# MB1297_MEMS.net
KiCad netlist of a schematic drawn in Altium Designer
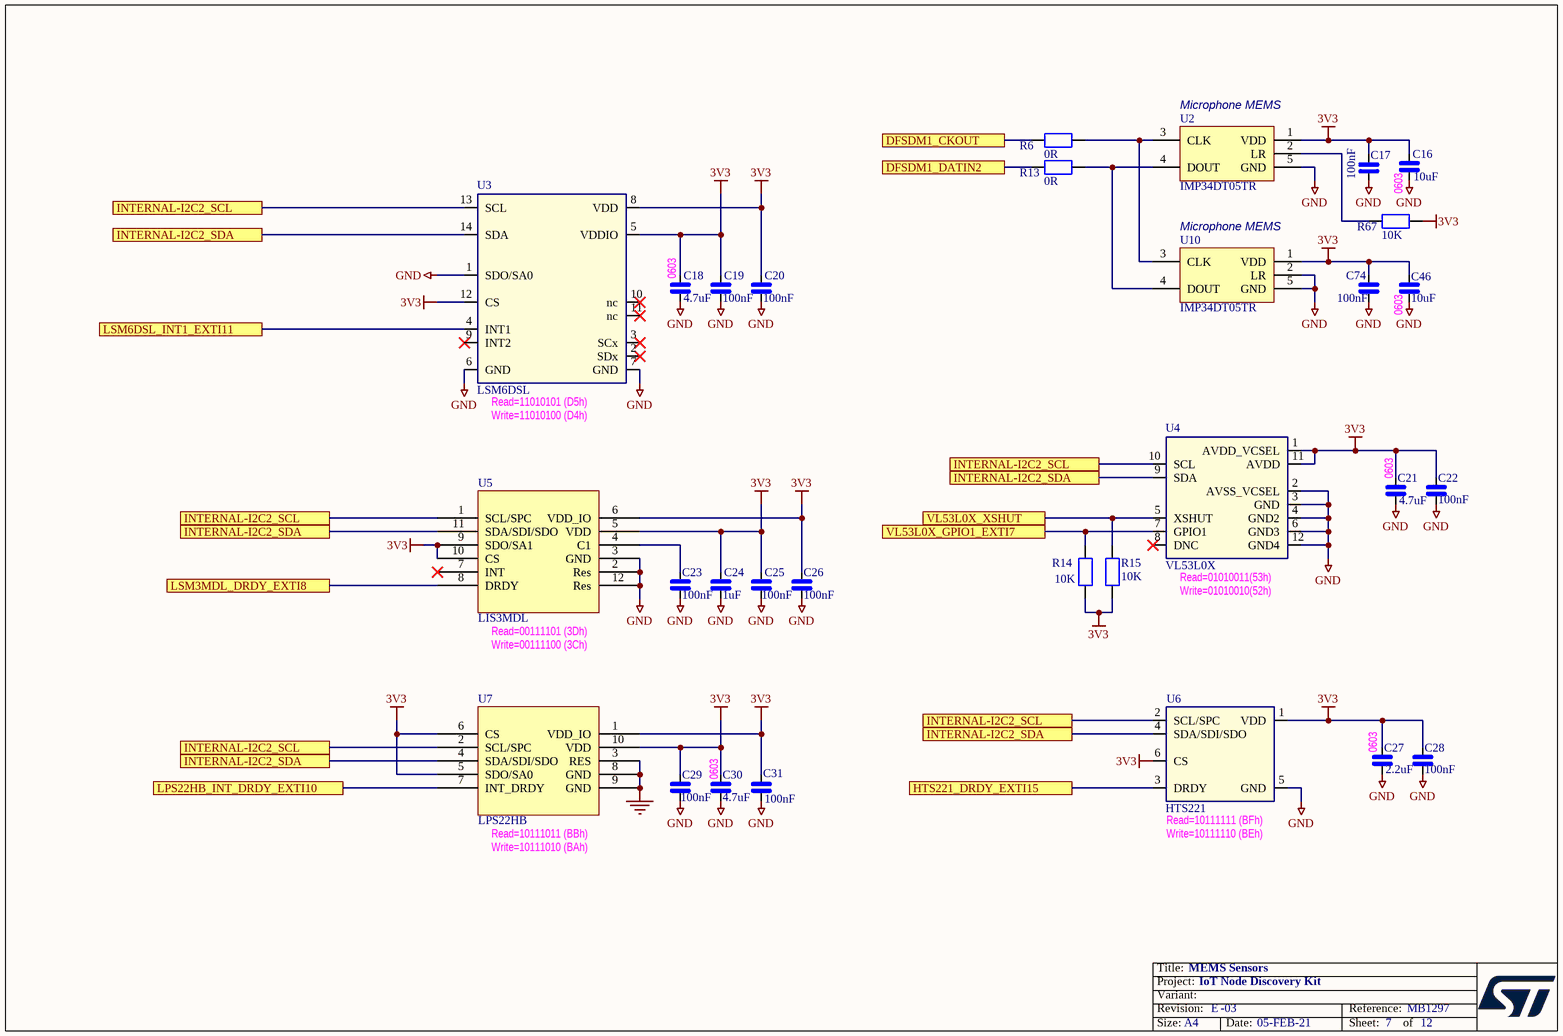
[diagram p0: MB1297_MEMS.SchDoc]

(export (version "E")
  (design (tool "Eeschema 10.0.6"))
  (components
    (comp (ref "C16")
      (value "10uF")
      (footprint "0603_CAP_NPOL")
      (description "Capacitor_not polarized")
      (libsource (lib "ST_Lib3D") (part "CAP_NPOL"))
    )
    (comp (ref "C17")
      (value "100nF")
      (footprint "0402")
      (description "Capacitor_not polarized")
      (libsource (lib "ST_Lib3D") (part "CAP_NPOL"))
    )
    (comp (ref "C18")
      (value "4.7uF")
      (footprint "0603_CAP_NPOL")
      (description "Capacitor_not polarized")
      (libsource (lib "ST_Lib3D") (part "CAP_NPOL"))
    )
    (comp (ref "C19")
      (value "100nF")
      (footprint "0402")
      (description "Capacitor_not polarized")
      (libsource (lib "ST_Lib3D") (part "CAP_NPOL"))
    )
    (comp (ref "C20")
      (value "100nF")
      (footprint "0402")
      (description "Capacitor_not polarized")
      (libsource (lib "ST_Lib3D") (part "CAP_NPOL"))
    )
    (comp (ref "C21")
      (value "4.7uF")
      (footprint "0603_CAP_NPOL")
      (description "Capacitor_not polarized")
      (libsource (lib "ST_Lib3D") (part "CAP_NPOL"))
    )
    (comp (ref "C22")
      (value "100nF")
      (footprint "0402")
      (description "Capacitor_not polarized")
      (libsource (lib "ST_Lib3D") (part "CAP_NPOL"))
    )
    (comp (ref "C23")
      (value "100nF")
      (footprint "0402")
      (description "Capacitor_not polarized")
      (libsource (lib "ST_Lib3D") (part "CAP_NPOL"))
    )
    (comp (ref "C24")
      (value "1uF")
      (footprint "0402")
      (description "Capacitor_not polarized")
      (libsource (lib "ST_Lib3D") (part "CAP_NPOL"))
    )
    (comp (ref "C25")
      (value "100nF")
      (footprint "0402")
      (description "Capacitor_not polarized")
      (libsource (lib "ST_Lib3D") (part "CAP_NPOL"))
    )
    (comp (ref "C26")
      (value "100nF")
      (footprint "0402")
      (description "Capacitor_not polarized")
      (libsource (lib "ST_Lib3D") (part "CAP_NPOL"))
    )
    (comp (ref "C27")
      (value "2.2uF")
      (footprint "0603_CAP_NPOL")
      (description "Capacitor_not polarized")
      (libsource (lib "ST_Lib3D") (part "CAP_NPOL"))
    )
    (comp (ref "C28")
      (value "100nF")
      (footprint "0402")
      (description "Capacitor_not polarized")
      (libsource (lib "ST_Lib3D") (part "CAP_NPOL"))
    )
    (comp (ref "C29")
      (value "100nF")
      (footprint "0402")
      (description "Capacitor_not polarized")
      (libsource (lib "ST_Lib3D") (part "CAP_NPOL"))
    )
    (comp (ref "C30")
      (value "4.7uF")
      (footprint "0603_CAP_NPOL")
      (description "Capacitor_not polarized")
      (libsource (lib "ST_Lib3D") (part "CAP_NPOL"))
    )
    (comp (ref "C31")
      (value "100nF")
      (footprint "0402")
      (description "Capacitor_not polarized")
      (libsource (lib "ST_Lib3D") (part "CAP_NPOL"))
    )
    (comp (ref "C46")
      (value "10uF")
      (footprint "0603_CAP_NPOL")
      (description "Capacitor_not polarized")
      (libsource (lib "MB1297") (part "CAP_NPOL"))
    )
    (comp (ref "C74")
      (value "100nF")
      (footprint "0402")
      (description "Capacitor_not polarized")
      (libsource (lib "MB1297") (part "CAP_NPOL"))
    )
    (comp (ref "R6")
      (value "0R")
      (footprint "0402")
      (description "Resistor")
      (libsource (lib "ST_Lib3D") (part "RES"))
    )
    (comp (ref "R13")
      (value "0R")
      (footprint "0402")
      (description "Resistor")
      (libsource (lib "ST_Lib3D") (part "RES"))
    )
    (comp (ref "R14")
      (value "10K")
      (footprint "0402")
      (description "Resistor")
      (libsource (lib "ST_Lib3D") (part "RES"))
    )
    (comp (ref "R15")
      (value "10K")
      (footprint "0402")
      (description "Resistor")
      (libsource (lib "ST_Lib3D") (part "RES"))
    )
    (comp (ref "R67")
      (value "10K")
      (footprint "0402")
      (description "Resistor")
      (libsource (lib "ST_Lib3D") (part "RES"))
    )
    (comp (ref "U2")
      (value "IMP34DT05TR")
      (footprint "HCLGA-4LD 3x4x1")
      (description "MEMS audio microphone")
      (libsource (lib "ST_Lib3D") (part "MP34DT01"))
    )
    (comp (ref "U3")
      (value "LSM6DSL")
      (footprint "LGA14L-2.5X3X0.86p0.5")
      (description "Accelero + Gyro MEMS (6 Axis)")
      (libsource (lib "ST_Lib3D") (part "LSM6DSL"))
    )
    (comp (ref "U4")
      (value "VL53L0X")
      (footprint "LGA12-optical")
      (description "Proximity sensor MEMS")
      (libsource (lib "ST_Lib3D") (part "VL53L0X"))
    )
    (comp (ref "U5")
      (value "LIS3MDL")
      (footprint "VFLGA12-2x2x1")
      (description "IC,Sensor")
      (fields (field (name "PROVIDER") "MMCC"))
      (libsource (lib "Semicon-ST") (part "LIS3MDL"))
    )
    (comp (ref "U6")
      (value "HTS221")
      (footprint "HLGA6L-2x2x0.9")
      (description "Humidity + Temp MEMS")
      (libsource (lib "ST_Lib3D") (part "HTS221"))
    )
    (comp (ref "U7")
      (value "LPS22HB")
      (footprint "HLGA10L-2X2X0.76")
      (description "IC,Sensor")
      (fields (field (name "PROVIDER") "MMCC"))
      (libsource (lib "ST_Lib3D") (part "LPS22HB"))
    )
    (comp (ref "U10")
      (value "IMP34DT05TR")
      (footprint "HCLGA-4LD 3x4x1")
      (description "MEMS audio microphone")
      (libsource (lib "MB1297") (part "MP34DT01"))
    )
  )
  (nets
    (net (code "1") (name "/DFSDM1_CKOUT") (class "Default")
      (node (ref "R6") (pin "2") (pinfunction "2_2") (pintype "passive"))
    )
    (net (code "2") (name "/DFSDM1_DATIN2") (class "Default")
      (node (ref "R13") (pin "2") (pinfunction "2_2") (pintype "passive"))
    )
    (net (code "3") (name "/HTS221_DRDY_EXTI15") (class "Default")
      (node (ref "U6") (pin "3") (pinfunction "DRDY_3") (pintype "passive"))
    )
    (net (code "4") (name "/INTERNAL-I2C2_SCL") (class "Default")
      (node (ref "U3") (pin "13") (pinfunction "SCL_13") (pintype "passive"))
      (node (ref "U4") (pin "10") (pinfunction "SCL_10") (pintype "passive"))
      (node (ref "U5") (pin "1") (pinfunction "SCL/SPC_1") (pintype "passive"))
      (node (ref "U6") (pin "2") (pinfunction "SCL/SPC_2") (pintype "passive"))
      (node (ref "U7") (pin "2") (pinfunction "SCL/SPC_2") (pintype "passive"))
    )
    (net (code "5") (name "/INTERNAL-I2C2_SDA") (class "Default")
      (node (ref "U3") (pin "14") (pinfunction "SDA_14") (pintype "passive"))
      (node (ref "U4") (pin "9") (pinfunction "SDA_9") (pintype "passive"))
      (node (ref "U5") (pin "11") (pinfunction "SDA/SDI/SDO_11") (pintype "passive"))
      (node (ref "U6") (pin "4") (pinfunction "SDA/SDI/SDO_4") (pintype "passive"))
      (node (ref "U7") (pin "4") (pinfunction "SDA/SDI/SDO_4") (pintype "passive"))
    )
    (net (code "6") (name "/LPS22HB_INT_DRDY_EXTI10") (class "Default")
      (node (ref "U7") (pin "7") (pinfunction "INT_DRDY_7") (pintype "passive"))
    )
    (net (code "7") (name "/LSM3MDL_DRDY_EXTI8") (class "Default")
      (node (ref "U5") (pin "8") (pinfunction "DRDY_8") (pintype "passive"))
    )
    (net (code "8") (name "/LSM6DSL_INT1_EXTI11") (class "Default")
      (node (ref "U3") (pin "4") (pinfunction "INT1_4") (pintype "passive"))
    )
    (net (code "9") (name "/VL53L0X_GPIO1_EXTI7") (class "Default")
      (node (ref "R14") (pin "2") (pinfunction "2_2") (pintype "passive"))
      (node (ref "U4") (pin "7") (pinfunction "GPIO1_7") (pintype "passive"))
    )
    (net (code "10") (name "/VL53L0X_XSHUT") (class "Default")
      (node (ref "R15") (pin "2") (pinfunction "2_2") (pintype "passive"))
      (node (ref "U4") (pin "5") (pinfunction "XSHUT_5") (pintype "passive"))
    )
    (net (code "11") (name "3V3") (class "Default")
      (node (ref "C16") (pin "1") (pinfunction "1_1") (pintype "passive"))
      (node (ref "C17") (pin "2") (pinfunction "2_2") (pintype "passive"))
      (node (ref "C18") (pin "1") (pinfunction "1_1") (pintype "passive"))
      (node (ref "C19") (pin "1") (pinfunction "1_1") (pintype "passive"))
      (node (ref "C20") (pin "1") (pinfunction "1_1") (pintype "passive"))
      (node (ref "C21") (pin "1") (pinfunction "1_1") (pintype "passive"))
      (node (ref "C22") (pin "1") (pinfunction "1_1") (pintype "passive"))
      (node (ref "C24") (pin "1") (pinfunction "1_1") (pintype "passive"))
      (node (ref "C25") (pin "1") (pinfunction "1_1") (pintype "passive"))
      (node (ref "C26") (pin "1") (pinfunction "1_1") (pintype "passive"))
      (node (ref "C27") (pin "1") (pinfunction "1_1") (pintype "passive"))
      (node (ref "C28") (pin "1") (pinfunction "1_1") (pintype "passive"))
      (node (ref "C29") (pin "1") (pinfunction "1_1") (pintype "passive"))
      (node (ref "C30") (pin "1") (pinfunction "1_1") (pintype "passive"))
      (node (ref "C31") (pin "1") (pinfunction "1_1") (pintype "passive"))
      (node (ref "C46") (pin "1") (pinfunction "1_1") (pintype "passive"))
      (node (ref "C74") (pin "1") (pinfunction "1_1") (pintype "passive"))
      (node (ref "R14") (pin "1") (pinfunction "1_1") (pintype "passive"))
      (node (ref "R15") (pin "1") (pinfunction "1_1") (pintype "passive"))
      (node (ref "R67") (pin "1") (pinfunction "1_1") (pintype "passive"))
      (node (ref "U10") (pin "1") (pinfunction "VDD_1") (pintype "passive"))
      (node (ref "U2") (pin "1") (pinfunction "VDD_1") (pintype "passive"))
      (node (ref "U3") (pin "12") (pinfunction "CS_12") (pintype "passive"))
      (node (ref "U3") (pin "5") (pinfunction "VDDIO_5") (pintype "passive"))
      (node (ref "U3") (pin "8") (pinfunction "VDD_8") (pintype "passive"))
      (node (ref "U4") (pin "1") (pinfunction "AVDD_VCSEL_1") (pintype "passive"))
      (node (ref "U4") (pin "11") (pinfunction "AVDD_11") (pintype "passive"))
      (node (ref "U5") (pin "10") (pinfunction "CS_10") (pintype "passive"))
      (node (ref "U5") (pin "5") (pinfunction "VDD_5") (pintype "passive"))
      (node (ref "U5") (pin "6") (pinfunction "VDD_IO_6") (pintype "passive"))
      (node (ref "U5") (pin "9") (pinfunction "SDO/SA1_9") (pintype "passive"))
      (node (ref "U6") (pin "1") (pinfunction "VDD_1") (pintype "passive"))
      (node (ref "U6") (pin "6") (pinfunction "CS_6") (pintype "passive"))
      (node (ref "U7") (pin "1") (pinfunction "VDD_IO_1") (pintype "passive"))
      (node (ref "U7") (pin "10") (pinfunction "VDD_10") (pintype "passive"))
      (node (ref "U7") (pin "5") (pinfunction "SDO/SA0_5") (pintype "passive"))
      (node (ref "U7") (pin "6") (pinfunction "CS_6") (pintype "passive"))
    )
    (net (code "12") (name "GND") (class "Default")
      (node (ref "C16") (pin "2") (pinfunction "2_2") (pintype "passive"))
      (node (ref "C17") (pin "1") (pinfunction "1_1") (pintype "passive"))
      (node (ref "C18") (pin "2") (pinfunction "2_2") (pintype "passive"))
      (node (ref "C19") (pin "2") (pinfunction "2_2") (pintype "passive"))
      (node (ref "C20") (pin "2") (pinfunction "2_2") (pintype "passive"))
      (node (ref "C21") (pin "2") (pinfunction "2_2") (pintype "passive"))
      (node (ref "C22") (pin "2") (pinfunction "2_2") (pintype "passive"))
      (node (ref "C23") (pin "2") (pinfunction "2_2") (pintype "passive"))
      (node (ref "C24") (pin "2") (pinfunction "2_2") (pintype "passive"))
      (node (ref "C25") (pin "2") (pinfunction "2_2") (pintype "passive"))
      (node (ref "C26") (pin "2") (pinfunction "2_2") (pintype "passive"))
      (node (ref "C27") (pin "2") (pinfunction "2_2") (pintype "passive"))
      (node (ref "C28") (pin "2") (pinfunction "2_2") (pintype "passive"))
      (node (ref "C29") (pin "2") (pinfunction "2_2") (pintype "passive"))
      (node (ref "C30") (pin "2") (pinfunction "2_2") (pintype "passive"))
      (node (ref "C31") (pin "2") (pinfunction "2_2") (pintype "passive"))
      (node (ref "C46") (pin "2") (pinfunction "2_2") (pintype "passive"))
      (node (ref "C74") (pin "2") (pinfunction "2_2") (pintype "passive"))
      (node (ref "U10") (pin "2") (pinfunction "LR_2") (pintype "passive"))
      (node (ref "U10") (pin "5") (pinfunction "GND_5") (pintype "passive"))
      (node (ref "U2") (pin "5") (pinfunction "GND_5") (pintype "passive"))
      (node (ref "U3") (pin "1") (pinfunction "SDO/SA0_1") (pintype "passive"))
      (node (ref "U3") (pin "6") (pinfunction "GND_6") (pintype "passive"))
      (node (ref "U3") (pin "7") (pinfunction "GND_7") (pintype "passive"))
      (node (ref "U4") (pin "12") (pinfunction "GND4_12") (pintype "passive"))
      (node (ref "U4") (pin "2") (pinfunction "AVSS_VCSEL_2") (pintype "passive"))
      (node (ref "U4") (pin "3") (pinfunction "GND_3") (pintype "passive"))
      (node (ref "U4") (pin "4") (pinfunction "GND2_4") (pintype "passive"))
      (node (ref "U4") (pin "6") (pinfunction "GND3_6") (pintype "passive"))
      (node (ref "U5") (pin "12") (pinfunction "Res_12") (pintype "passive"))
      (node (ref "U5") (pin "2") (pinfunction "Res_2") (pintype "passive"))
      (node (ref "U5") (pin "3") (pinfunction "GND_3") (pintype "passive"))
      (node (ref "U6") (pin "5") (pinfunction "GND_5") (pintype "passive"))
      (node (ref "U7") (pin "3") (pinfunction "RES_3") (pintype "passive"))
      (node (ref "U7") (pin "8") (pinfunction "GND_8") (pintype "passive"))
      (node (ref "U7") (pin "9") (pinfunction "GND_9") (pintype "passive"))
    )
    (net (code "13") (name "Net-(U2-LR)") (class "Default")
      (node (ref "R67") (pin "2") (pinfunction "2_2") (pintype "passive"))
      (node (ref "U2") (pin "2") (pinfunction "LR_2") (pintype "passive"))
    )
    (net (code "14") (name "Net-(U5-C1)") (class "Default")
      (node (ref "C23") (pin "1") (pinfunction "1_1") (pintype "passive"))
      (node (ref "U5") (pin "4") (pinfunction "C1_4") (pintype "passive"))
    )
    (net (code "15") (name "Net-(U10-CLK)") (class "Default")
      (node (ref "R6") (pin "1") (pinfunction "1_1") (pintype "passive"))
      (node (ref "U10") (pin "3") (pinfunction "CLK_3") (pintype "passive"))
      (node (ref "U2") (pin "3") (pinfunction "CLK_3") (pintype "passive"))
    )
    (net (code "16") (name "Net-(U10-DOUT)") (class "Default")
      (node (ref "R13") (pin "1") (pinfunction "1_1") (pintype "passive"))
      (node (ref "U10") (pin "4") (pinfunction "DOUT_4") (pintype "passive"))
      (node (ref "U2") (pin "4") (pinfunction "DOUT_4") (pintype "passive"))
    )
    (net (code "17") (name "unconnected-(U3-INT2-Pad9)") (class "Default")
      (node (ref "U3") (pin "9") (pinfunction "INT2_9") (pintype "passive+no_connect"))
    )
    (net (code "18") (name "unconnected-(U3-SCx-Pad3)") (class "Default")
      (node (ref "U3") (pin "3") (pinfunction "SCx_3") (pintype "passive+no_connect"))
    )
    (net (code "19") (name "unconnected-(U3-SDx-Pad2)") (class "Default")
      (node (ref "U3") (pin "2") (pinfunction "SDx_2") (pintype "passive+no_connect"))
    )
    (net (code "20") (name "unconnected-(U3-nc-Pad10)") (class "Default")
      (node (ref "U3") (pin "10") (pinfunction "nc_10") (pintype "passive+no_connect"))
    )
    (net (code "21") (name "unconnected-(U3-nc-Pad11)") (class "Default")
      (node (ref "U3") (pin "11") (pinfunction "nc_11") (pintype "passive+no_connect"))
    )
    (net (code "22") (name "unconnected-(U4-DNC-Pad8)") (class "Default")
      (node (ref "U4") (pin "8") (pinfunction "DNC_8") (pintype "passive+no_connect"))
    )
    (net (code "23") (name "unconnected-(U5-INT-Pad7)") (class "Default")
      (node (ref "U5") (pin "7") (pinfunction "INT_7") (pintype "passive+no_connect"))
    )
  )
)
